# v1_r0.net
KiCad netlist of a schematic drawn in EAGLE
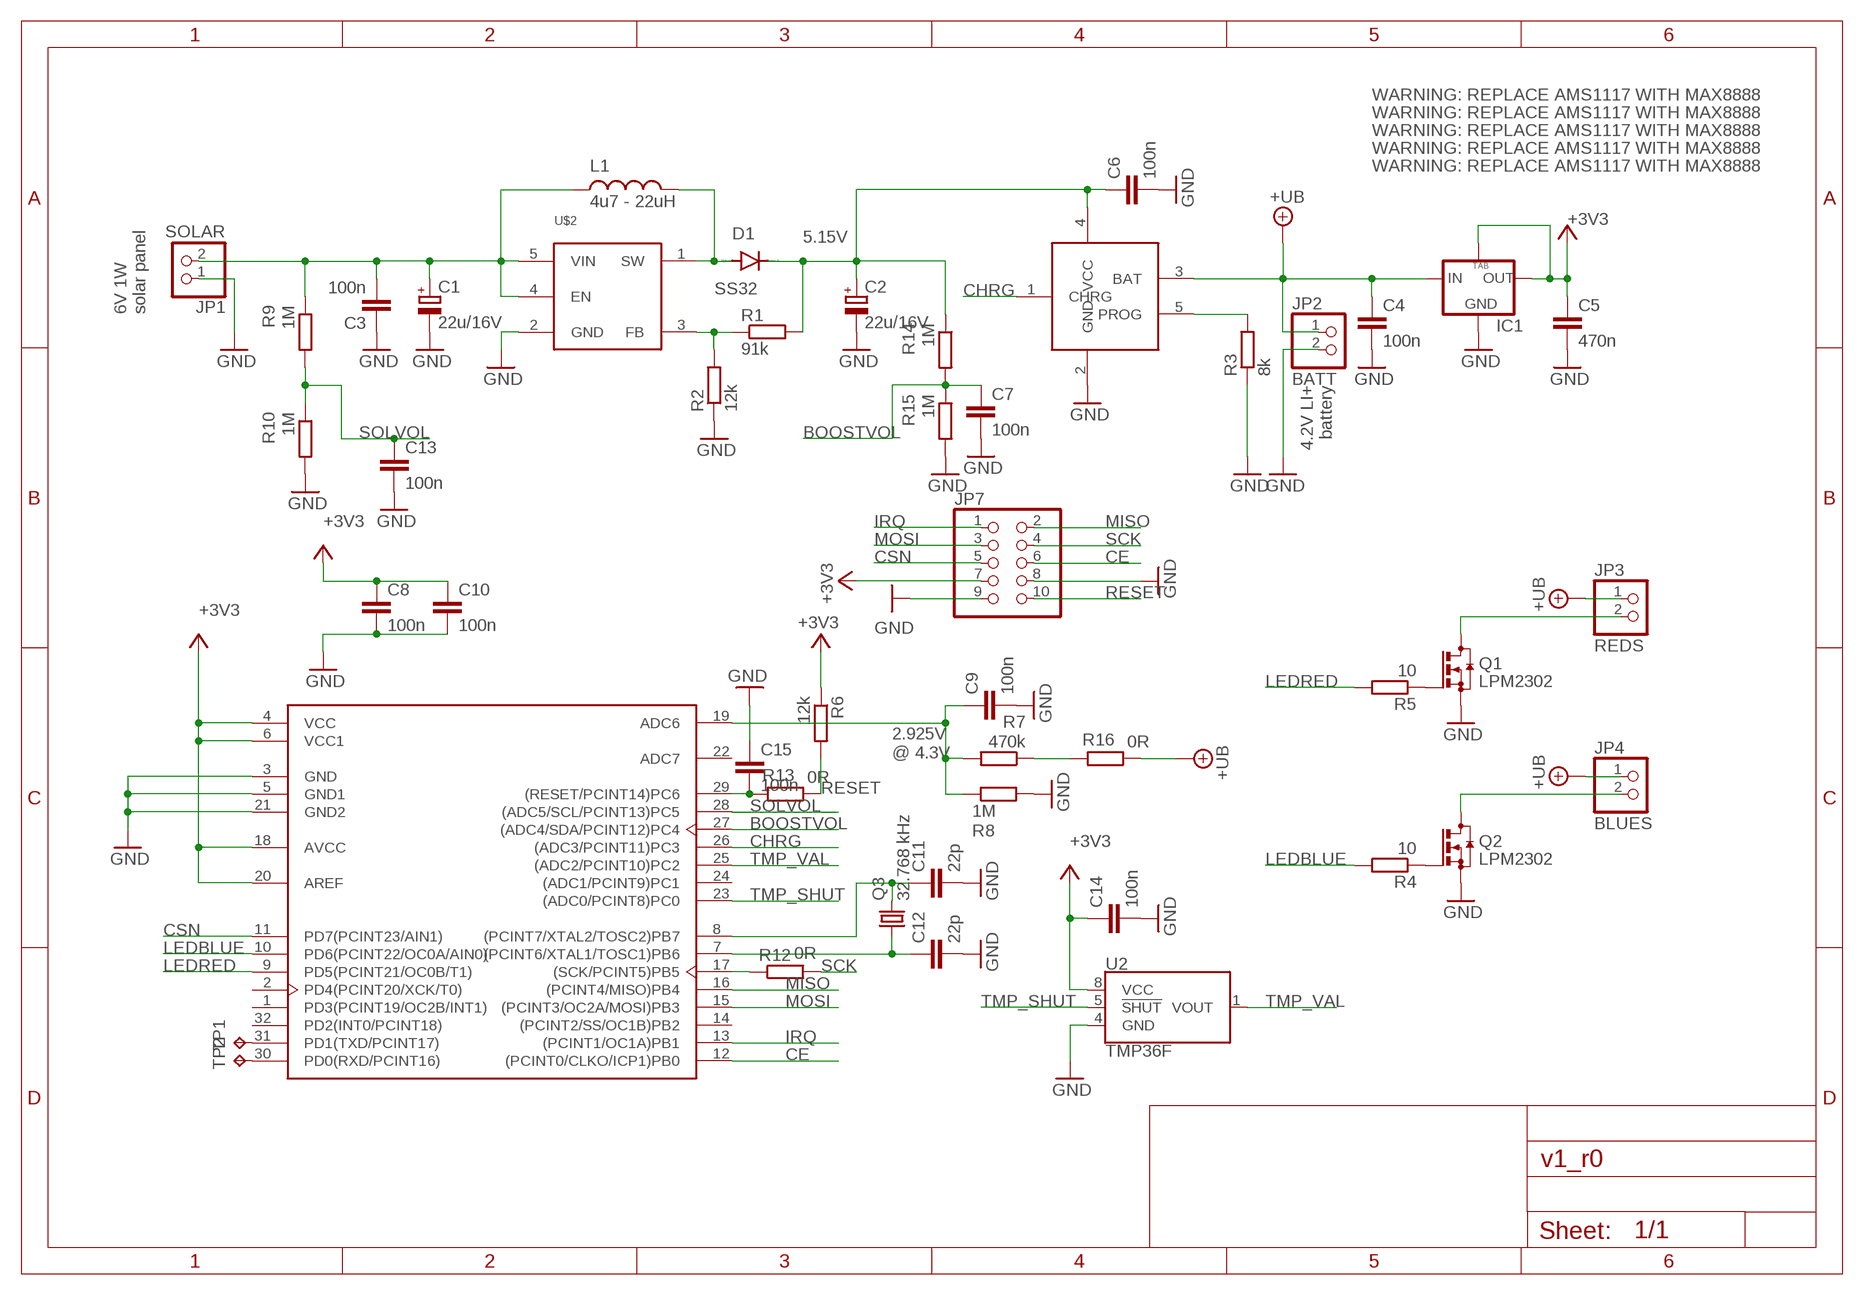
[diagram p0: schematic, sheet 1]

(export (version "E")
  (design (tool "Eeschema 10.0.6"))
  (components
    (comp (ref "C1")
      (value "22u/16V")
      (footprint "eagle-import:CT6032")
      (libsource (lib "eagle-import") (part "CPOL-EUCT6032"))
    )
    (comp (ref "C2")
      (value "22u/16V")
      (footprint "eagle-import:CT6032")
      (libsource (lib "eagle-import") (part "CPOL-EUCT6032"))
    )
    (comp (ref "C3")
      (value "100n")
      (footprint "eagle-import:C0603")
      (libsource (lib "eagle-import") (part "C-EUC0603"))
    )
    (comp (ref "C4")
      (value "100n")
      (footprint "eagle-import:C0603")
      (libsource (lib "eagle-import") (part "C-EUC0603"))
    )
    (comp (ref "C5")
      (value "470n")
      (footprint "eagle-import:C0603")
      (libsource (lib "eagle-import") (part "C-EUC0603"))
    )
    (comp (ref "C6")
      (value "100n")
      (footprint "eagle-import:C0603")
      (libsource (lib "eagle-import") (part "C-EUC0603"))
    )
    (comp (ref "C7")
      (value "100n")
      (footprint "eagle-import:C0603")
      (libsource (lib "eagle-import") (part "C-EUC0603"))
    )
    (comp (ref "C8")
      (value "100n")
      (footprint "eagle-import:C0603")
      (libsource (lib "eagle-import") (part "C-EUC0603"))
    )
    (comp (ref "C9")
      (value "100n")
      (footprint "eagle-import:C0603")
      (libsource (lib "eagle-import") (part "C-EUC0603"))
    )
    (comp (ref "C10")
      (value "100n")
      (footprint "eagle-import:C0603")
      (libsource (lib "eagle-import") (part "C-EUC0603"))
    )
    (comp (ref "C11")
      (value "22p")
      (footprint "eagle-import:C0603")
      (libsource (lib "eagle-import") (part "C-EUC0603"))
    )
    (comp (ref "C12")
      (value "22p")
      (footprint "eagle-import:C0603")
      (libsource (lib "eagle-import") (part "C-EUC0603"))
    )
    (comp (ref "C13")
      (value "100n")
      (footprint "eagle-import:C0603")
      (libsource (lib "eagle-import") (part "C-EUC0603"))
    )
    (comp (ref "C14")
      (value "100n")
      (footprint "eagle-import:C0603")
      (libsource (lib "eagle-import") (part "C-EUC0603"))
    )
    (comp (ref "C15")
      (value "100n")
      (footprint "eagle-import:C0603")
      (libsource (lib "eagle-import") (part "C-EUC0603"))
    )
    (comp (ref "D1")
      (value "SS32")
      (footprint "eagle-import:SMB")
      (libsource (lib "eagle-import") (part "ES2D"))
    )
    (comp (ref "IC1")
      (value "LM1117")
      (footprint "eagle-import:SOT223")
      (libsource (lib "eagle-import") (part "LM1117"))
    )
    (comp (ref "JP1")
      (value "SOLAR")
      (footprint "eagle-import:1X02")
      (libsource (lib "eagle-import") (part "PINHD-1X2"))
    )
    (comp (ref "JP2")
      (value "BATT")
      (footprint "eagle-import:1X02")
      (libsource (lib "eagle-import") (part "PINHD-1X2"))
    )
    (comp (ref "JP3")
      (value "REDS")
      (footprint "eagle-import:1X02")
      (libsource (lib "eagle-import") (part "PINHD-1X2"))
    )
    (comp (ref "JP4")
      (value "BLUES")
      (footprint "eagle-import:1X02")
      (libsource (lib "eagle-import") (part "PINHD-1X2"))
    )
    (comp (ref "JP7")
      (value "PINHD-2X5")
      (footprint "eagle-import:2X05")
      (libsource (lib "eagle-import") (part "PINHD-2X5"))
    )
    (comp (ref "L1")
      (value "4u7 - 22uH")
      (footprint "eagle-import:DS1608")
      (libsource (lib "eagle-import") (part "DS1608C"))
    )
    (comp (ref "Q1")
      (value "LPM2302")
      (footprint "eagle-import:SOT23")
      (libsource (lib "eagle-import") (part "BSS123"))
    )
    (comp (ref "Q2")
      (value "LPM2302")
      (footprint "eagle-import:SOT23")
      (libsource (lib "eagle-import") (part "BSS123"))
    )
    (comp (ref "Q3")
      (value "32.768 kHz")
      (footprint "eagle-import:CTS406")
      (libsource (lib "eagle-import") (part "CRYSTALCTS406"))
    )
    (comp (ref "R1")
      (value "91k")
      (footprint "eagle-import:R0603")
      (libsource (lib "eagle-import") (part "R-EU_R0603"))
    )
    (comp (ref "R2")
      (value "12k")
      (footprint "eagle-import:R0603")
      (libsource (lib "eagle-import") (part "R-EU_R0603"))
    )
    (comp (ref "R3")
      (value "8k")
      (footprint "eagle-import:R0603")
      (libsource (lib "eagle-import") (part "R-EU_R0603"))
    )
    (comp (ref "R4")
      (value "10")
      (footprint "eagle-import:R0603")
      (libsource (lib "eagle-import") (part "R-EU_R0603"))
    )
    (comp (ref "R5")
      (value "10")
      (footprint "eagle-import:R0603")
      (libsource (lib "eagle-import") (part "R-EU_R0603"))
    )
    (comp (ref "R6")
      (value "12k")
      (footprint "eagle-import:R0603")
      (libsource (lib "eagle-import") (part "R-EU_R0603"))
    )
    (comp (ref "R7")
      (value "470k")
      (footprint "eagle-import:R0603")
      (libsource (lib "eagle-import") (part "R-EU_R0603"))
    )
    (comp (ref "R8")
      (value "1M")
      (footprint "eagle-import:R0603")
      (libsource (lib "eagle-import") (part "R-EU_R0603"))
    )
    (comp (ref "R9")
      (value "1M")
      (footprint "eagle-import:R0603")
      (libsource (lib "eagle-import") (part "R-EU_R0603"))
    )
    (comp (ref "R10")
      (value "1M")
      (footprint "eagle-import:R0603")
      (libsource (lib "eagle-import") (part "R-EU_R0603"))
    )
    (comp (ref "R12")
      (value "0R")
      (footprint "eagle-import:0204_5")
      (libsource (lib "eagle-import") (part "resistor_348_R-EU_0204/5"))
    )
    (comp (ref "R13")
      (value "0R")
      (footprint "eagle-import:0204_5")
      (libsource (lib "eagle-import") (part "resistor_348_R-EU_0204/5"))
    )
    (comp (ref "R14")
      (value "1M")
      (footprint "eagle-import:R0603")
      (libsource (lib "eagle-import") (part "R-EU_R0603"))
    )
    (comp (ref "R15")
      (value "1M")
      (footprint "eagle-import:R0603")
      (libsource (lib "eagle-import") (part "R-EU_R0603"))
    )
    (comp (ref "R16")
      (value "0R")
      (footprint "eagle-import:0204_5")
      (libsource (lib "eagle-import") (part "resistor_348_R-EU_0204/5"))
    )
    (comp (ref "TP1")
      (value "TPB1,27")
      (footprint "eagle-import:B1,27")
      (libsource (lib "eagle-import") (part "TPB1,27"))
    )
    (comp (ref "TP2")
      (value "TPB1,27")
      (footprint "eagle-import:B1,27")
      (libsource (lib "eagle-import") (part "TPB1,27"))
    )
    (comp (ref "U$1")
      (value "LTC4054")
      (footprint "eagle-import:LTC4054")
      (libsource (lib "eagle-import") (part "LTC4054"))
    )
    (comp (ref "U$2")
      (value "SB6284")
      (footprint "eagle-import:SOT23-6")
      (libsource (lib "eagle-import") (part "SB6284"))
    )
    (comp (ref "U1")
      (value "ATMEGA*")
      (footprint "eagle-import:TQFP-32")
      (fields
        (field (name "DIGIKEY_PART_NUMBER") "ATMEGA328P-AU-ND")
        (field (name "MANUFACTURER") "Microchip Technology")
        (field (name "MPN") "ATMEGA328P-AU")
        (field (name "CREATED_BY") "PCBLayout.com")
      )
      (libsource (lib "eagle-import") (part "ATMEGA328P-AU"))
    )
    (comp (ref "U2")
      (value "TMP36F")
      (footprint "eagle-import:SOIC-8")
      (libsource (lib "eagle-import") (part "TMP36"))
    )
  )
  (nets
    (net (code "1") (name "+3V3") (class "Default")
      (node (ref "C10") (pin "1") (pinfunction "1_1") (pintype "passive"))
      (node (ref "C14") (pin "1") (pinfunction "1_1") (pintype "passive"))
      (node (ref "C5") (pin "1") (pinfunction "1_1") (pintype "passive"))
      (node (ref "C8") (pin "1") (pinfunction "1_1") (pintype "passive"))
      (node (ref "IC1") (pin "2") (pinfunction "OUT_2") (pintype "passive"))
      (node (ref "IC1") (pin "4") (pinfunction "TAB_4") (pintype "passive"))
      (node (ref "JP7") (pin "7") (pinfunction "7_7") (pintype "passive"))
      (node (ref "R6") (pin "1") (pinfunction "1_1") (pintype "passive"))
      (node (ref "U1") (pin "18") (pinfunction "AVCC_18") (pintype "power_in"))
      (node (ref "U1") (pin "20") (pinfunction "AREF_20") (pintype "power_in"))
      (node (ref "U1") (pin "4") (pinfunction "VCC_4") (pintype "power_in"))
      (node (ref "U1") (pin "6") (pinfunction "VCC1_6") (pintype "power_in"))
      (node (ref "U2") (pin "8") (pinfunction "VCC_8") (pintype "bidirectional"))
    )
    (net (code "2") (name "+UB") (class "Default")
      (node (ref "C4") (pin "1") (pinfunction "1_1") (pintype "passive"))
      (node (ref "IC1") (pin "3") (pinfunction "IN_3") (pintype "input"))
      (node (ref "JP2") (pin "1") (pinfunction "1_1") (pintype "passive"))
      (node (ref "JP3") (pin "1") (pinfunction "1_1") (pintype "passive"))
      (node (ref "JP4") (pin "1") (pinfunction "1_1") (pintype "passive"))
      (node (ref "R16") (pin "1") (pinfunction "1_1") (pintype "passive"))
      (node (ref "U$1") (pin "3") (pinfunction "BAT_3") (pintype "output"))
    )
    (net (code "3") (name "/BOOSTVOL") (class "Default")
      (node (ref "C7") (pin "1") (pinfunction "1_1") (pintype "passive"))
      (node (ref "R14") (pin "2") (pinfunction "2_2") (pintype "passive"))
      (node (ref "R15") (pin "1") (pinfunction "1_1") (pintype "passive"))
      (node (ref "U1") (pin "27") (pinfunction "(ADC4/SDA/PCINT12)PC4_27") (pintype "bidirectional"))
    )
    (net (code "4") (name "/CE") (class "Default")
      (node (ref "JP7") (pin "6") (pinfunction "6_6") (pintype "passive"))
      (node (ref "U1") (pin "12") (pinfunction "(PCINT0/CLKO/ICP1)PB0_12") (pintype "bidirectional"))
    )
    (net (code "5") (name "/CHRG") (class "Default")
      (node (ref "U$1") (pin "1") (pinfunction "CHRG_1") (pintype "bidirectional"))
      (node (ref "U1") (pin "26") (pinfunction "(ADC3/PCINT11)PC3_26") (pintype "bidirectional"))
    )
    (net (code "6") (name "/CSN") (class "Default")
      (node (ref "JP7") (pin "5") (pinfunction "5_5") (pintype "passive"))
      (node (ref "U1") (pin "11") (pinfunction "PD7(PCINT23/AIN1)_11") (pintype "bidirectional"))
    )
    (net (code "7") (name "/IRQ") (class "Default")
      (node (ref "JP7") (pin "1") (pinfunction "1_1") (pintype "passive"))
      (node (ref "U1") (pin "13") (pinfunction "(PCINT1/OC1A)PB1_13") (pintype "bidirectional"))
    )
    (net (code "8") (name "/LEDBLUE") (class "Default")
      (node (ref "R4") (pin "2") (pinfunction "2_2") (pintype "passive"))
      (node (ref "U1") (pin "10") (pinfunction "PD6(PCINT22/OC0A/AIN0)_10") (pintype "bidirectional"))
    )
    (net (code "9") (name "/LEDRED") (class "Default")
      (node (ref "R5") (pin "2") (pinfunction "2_2") (pintype "passive"))
      (node (ref "U1") (pin "9") (pinfunction "PD5(PCINT21/OC0B/T1)_9") (pintype "bidirectional"))
    )
    (net (code "10") (name "/MISO") (class "Default")
      (node (ref "JP7") (pin "2") (pinfunction "2_2") (pintype "passive"))
      (node (ref "U1") (pin "16") (pinfunction "(PCINT4/MISO)PB4_16") (pintype "bidirectional"))
    )
    (net (code "11") (name "/MOSI") (class "Default")
      (node (ref "JP7") (pin "3") (pinfunction "3_3") (pintype "passive"))
      (node (ref "U1") (pin "15") (pinfunction "(PCINT3/OC2A/MOSI)PB3_15") (pintype "bidirectional"))
    )
    (net (code "12") (name "/RESET") (class "Default")
      (node (ref "JP7") (pin "10") (pinfunction "10_10") (pintype "passive"))
      (node (ref "R13") (pin "1") (pinfunction "1_1") (pintype "passive"))
      (node (ref "R6") (pin "2") (pinfunction "2_2") (pintype "passive"))
    )
    (net (code "13") (name "/SCK") (class "Default")
      (node (ref "JP7") (pin "4") (pinfunction "4_4") (pintype "passive"))
      (node (ref "R12") (pin "2") (pinfunction "2_2") (pintype "passive"))
    )
    (net (code "14") (name "/SOLVOL") (class "Default")
      (node (ref "C13") (pin "1") (pinfunction "1_1") (pintype "passive"))
      (node (ref "R10") (pin "1") (pinfunction "1_1") (pintype "passive"))
      (node (ref "R9") (pin "2") (pinfunction "2_2") (pintype "passive"))
      (node (ref "U1") (pin "28") (pinfunction "(ADC5/SCL/PCINT13)PC5_28") (pintype "bidirectional"))
    )
    (net (code "15") (name "/TMP_SHUT") (class "Default")
      (node (ref "U1") (pin "23") (pinfunction "(ADC0/PCINT8)PC0_23") (pintype "bidirectional"))
      (node (ref "U2") (pin "5") (pinfunction "~{SHUT}_5") (pintype "bidirectional"))
    )
    (net (code "16") (name "/TMP_VAL") (class "Default")
      (node (ref "U1") (pin "25") (pinfunction "(ADC2/PCINT10)PC2_25") (pintype "bidirectional"))
      (node (ref "U2") (pin "1") (pinfunction "VOUT_1") (pintype "bidirectional"))
    )
    (net (code "17") (name "GND") (class "Default")
      (node (ref "C1") (pin "-") (pinfunction "-_-") (pintype "passive"))
      (node (ref "C10") (pin "2") (pinfunction "2_2") (pintype "passive"))
      (node (ref "C11") (pin "2") (pinfunction "2_2") (pintype "passive"))
      (node (ref "C12") (pin "2") (pinfunction "2_2") (pintype "passive"))
      (node (ref "C13") (pin "2") (pinfunction "2_2") (pintype "passive"))
      (node (ref "C14") (pin "2") (pinfunction "2_2") (pintype "passive"))
      (node (ref "C15") (pin "1") (pinfunction "1_1") (pintype "passive"))
      (node (ref "C2") (pin "-") (pinfunction "-_-") (pintype "passive"))
      (node (ref "C3") (pin "1") (pinfunction "1_1") (pintype "passive"))
      (node (ref "C4") (pin "2") (pinfunction "2_2") (pintype "passive"))
      (node (ref "C5") (pin "2") (pinfunction "2_2") (pintype "passive"))
      (node (ref "C6") (pin "2") (pinfunction "2_2") (pintype "passive"))
      (node (ref "C7") (pin "2") (pinfunction "2_2") (pintype "passive"))
      (node (ref "C8") (pin "2") (pinfunction "2_2") (pintype "passive"))
      (node (ref "C9") (pin "2") (pinfunction "2_2") (pintype "passive"))
      (node (ref "IC1") (pin "1") (pinfunction "GND_1") (pintype "input"))
      (node (ref "JP1") (pin "1") (pinfunction "1_1") (pintype "passive"))
      (node (ref "JP2") (pin "2") (pinfunction "2_2") (pintype "passive"))
      (node (ref "JP7") (pin "8") (pinfunction "8_8") (pintype "passive"))
      (node (ref "JP7") (pin "9") (pinfunction "9_9") (pintype "passive"))
      (node (ref "Q1") (pin "2") (pinfunction "S_2") (pintype "passive"))
      (node (ref "Q2") (pin "2") (pinfunction "S_2") (pintype "passive"))
      (node (ref "R10") (pin "2") (pinfunction "2_2") (pintype "passive"))
      (node (ref "R15") (pin "2") (pinfunction "2_2") (pintype "passive"))
      (node (ref "R2") (pin "1") (pinfunction "1_1") (pintype "passive"))
      (node (ref "R3") (pin "1") (pinfunction "1_1") (pintype "passive"))
      (node (ref "R8") (pin "2") (pinfunction "2_2") (pintype "passive"))
      (node (ref "U$1") (pin "2") (pinfunction "GND_2") (pintype "power_in"))
      (node (ref "U$2") (pin "2") (pinfunction "GND_2") (pintype "bidirectional"))
      (node (ref "U1") (pin "21") (pinfunction "GND2_21") (pintype "power_in"))
      (node (ref "U1") (pin "3") (pinfunction "GND_3") (pintype "power_in"))
      (node (ref "U1") (pin "5") (pinfunction "GND1_5") (pintype "power_in"))
      (node (ref "U2") (pin "4") (pinfunction "GND_4") (pintype "bidirectional"))
    )
    (net (code "18") (name "Net-(Q1-D)") (class "Default")
      (node (ref "JP3") (pin "2") (pinfunction "2_2") (pintype "passive"))
      (node (ref "Q1") (pin "3") (pinfunction "D_3") (pintype "passive"))
    )
    (net (code "19") (name "Net-(Q1-G)") (class "Default")
      (node (ref "Q1") (pin "1") (pinfunction "G_1") (pintype "passive"))
      (node (ref "R5") (pin "1") (pinfunction "1_1") (pintype "passive"))
    )
    (net (code "20") (name "Net-(Q2-D)") (class "Default")
      (node (ref "JP4") (pin "2") (pinfunction "2_2") (pintype "passive"))
      (node (ref "Q2") (pin "3") (pinfunction "D_3") (pintype "passive"))
    )
    (net (code "21") (name "Net-(Q2-G)") (class "Default")
      (node (ref "Q2") (pin "1") (pinfunction "G_1") (pintype "passive"))
      (node (ref "R4") (pin "1") (pinfunction "1_1") (pintype "passive"))
    )
    (net (code "22") (name "Net-(Q3-2)") (class "Default")
      (node (ref "C11") (pin "1") (pinfunction "1_1") (pintype "passive"))
      (node (ref "Q3") (pin "3") (pinfunction "2_3") (pintype "passive"))
      (node (ref "U1") (pin "8") (pinfunction "(PCINT7/XTAL2/TOSC2)PB7_8") (pintype "bidirectional"))
    )
    (net (code "23") (name "Net-(R16-Pad2)") (class "Default")
      (node (ref "R16") (pin "2") (pinfunction "2_2") (pintype "passive"))
      (node (ref "R7") (pin "1") (pinfunction "1_1") (pintype "passive"))
    )
    (net (code "24") (name "Net-(U$1-PROG)") (class "Default")
      (node (ref "R3") (pin "2") (pinfunction "2_2") (pintype "passive"))
      (node (ref "U$1") (pin "5") (pinfunction "PROG_5") (pintype "bidirectional"))
    )
    (net (code "25") (name "Net-(U$1-VCC)") (class "Default")
      (node (ref "C2") (pin "+") (pinfunction "+_+") (pintype "passive"))
      (node (ref "C6") (pin "1") (pinfunction "1_1") (pintype "passive"))
      (node (ref "D1") (pin "C") (pinfunction "C_C") (pintype "passive"))
      (node (ref "R1") (pin "2") (pinfunction "2_2") (pintype "passive"))
      (node (ref "R14") (pin "1") (pinfunction "1_1") (pintype "passive"))
      (node (ref "U$1") (pin "4") (pinfunction "VCC_4") (pintype "power_in"))
    )
    (net (code "26") (name "Net-(U$2-EN)") (class "Default")
      (node (ref "C1") (pin "+") (pinfunction "+_+") (pintype "passive"))
      (node (ref "C3") (pin "2") (pinfunction "2_2") (pintype "passive"))
      (node (ref "JP1") (pin "2") (pinfunction "2_2") (pintype "passive"))
      (node (ref "L1") (pin "P$2") (pinfunction "P$2_P$2") (pintype "passive"))
      (node (ref "R9") (pin "1") (pinfunction "1_1") (pintype "passive"))
      (node (ref "U$2") (pin "4") (pinfunction "EN_4") (pintype "bidirectional"))
      (node (ref "U$2") (pin "5") (pinfunction "VIN_5") (pintype "power_in"))
    )
    (net (code "27") (name "Net-(U$2-FB)") (class "Default")
      (node (ref "R1") (pin "1") (pinfunction "1_1") (pintype "passive"))
      (node (ref "R2") (pin "2") (pinfunction "2_2") (pintype "passive"))
      (node (ref "U$2") (pin "3") (pinfunction "FB_3") (pintype "bidirectional"))
    )
    (net (code "28") (name "Net-(U$2-SW)") (class "Default")
      (node (ref "D1") (pin "A") (pinfunction "A_A") (pintype "passive"))
      (node (ref "L1") (pin "P$1") (pinfunction "P$1_P$1") (pintype "passive"))
      (node (ref "U$2") (pin "1") (pinfunction "SW_1") (pintype "bidirectional"))
    )
    (net (code "29") (name "Net-(U1-(PCINT6{slash}XTAL1{slash}TOSC1)PB6)") (class "Default")
      (node (ref "C12") (pin "1") (pinfunction "1_1") (pintype "passive"))
      (node (ref "Q3") (pin "1") (pinfunction "1_1") (pintype "passive"))
      (node (ref "U1") (pin "7") (pinfunction "(PCINT6/XTAL1/TOSC1)PB6_7") (pintype "bidirectional"))
    )
    (net (code "30") (name "Net-(U1-(RESET{slash}PCINT14)PC6)") (class "Default")
      (node (ref "C15") (pin "2") (pinfunction "2_2") (pintype "passive"))
      (node (ref "R13") (pin "2") (pinfunction "2_2") (pintype "passive"))
      (node (ref "U1") (pin "29") (pinfunction "(RESET/PCINT14)PC6_29") (pintype "bidirectional"))
    )
    (net (code "31") (name "Net-(U1-(SCK{slash}PCINT5)PB5)") (class "Default")
      (node (ref "R12") (pin "1") (pinfunction "1_1") (pintype "passive"))
      (node (ref "U1") (pin "17") (pinfunction "(SCK/PCINT5)PB5_17") (pintype "bidirectional"))
    )
    (net (code "32") (name "Net-(U1-ADC6)") (class "Default")
      (node (ref "C9") (pin "1") (pinfunction "1_1") (pintype "passive"))
      (node (ref "R7") (pin "2") (pinfunction "2_2") (pintype "passive"))
      (node (ref "R8") (pin "1") (pinfunction "1_1") (pintype "passive"))
      (node (ref "U1") (pin "19") (pinfunction "ADC6_19") (pintype "input"))
    )
    (net (code "33") (name "Net-(U1-PD0(RXD{slash}PCINT16))") (class "Default")
      (node (ref "TP2") (pin "TP") (pinfunction "TP_TP") (pintype "input"))
      (node (ref "U1") (pin "30") (pinfunction "PD0(RXD/PCINT16)_30") (pintype "bidirectional"))
    )
    (net (code "34") (name "Net-(U1-PD1(TXD{slash}PCINT17))") (class "Default")
      (node (ref "TP1") (pin "TP") (pinfunction "TP_TP") (pintype "input"))
      (node (ref "U1") (pin "31") (pinfunction "PD1(TXD/PCINT17)_31") (pintype "bidirectional"))
    )
    (net (code "35") (name "unconnected-(U1-(ADC1{slash}PCINT9)PC1-Pad24)") (class "Default")
      (node (ref "U1") (pin "24") (pinfunction "(ADC1/PCINT9)PC1_24") (pintype "bidirectional"))
    )
    (net (code "36") (name "unconnected-(U1-(PCINT2{slash}SS{slash}OC1B)PB2-Pad14)") (class "Default")
      (node (ref "U1") (pin "14") (pinfunction "(PCINT2/SS/OC1B)PB2_14") (pintype "bidirectional"))
    )
    (net (code "37") (name "unconnected-(U1-ADC7-Pad22)") (class "Default")
      (node (ref "U1") (pin "22") (pinfunction "ADC7_22") (pintype "input"))
    )
    (net (code "38") (name "unconnected-(U1-PD2(INT0{slash}PCINT18)-Pad32)") (class "Default")
      (node (ref "U1") (pin "32") (pinfunction "PD2(INT0/PCINT18)_32") (pintype "bidirectional"))
    )
    (net (code "39") (name "unconnected-(U1-PD3(PCINT19{slash}OC2B{slash}INT1)-Pad1)") (class "Default")
      (node (ref "U1") (pin "1") (pinfunction "PD3(PCINT19/OC2B/INT1)_1") (pintype "bidirectional"))
    )
    (net (code "40") (name "unconnected-(U1-PD4(PCINT20{slash}XCK{slash}T0)-Pad2)") (class "Default")
      (node (ref "U1") (pin "2") (pinfunction "PD4(PCINT20/XCK/T0)_2") (pintype "bidirectional"))
    )
  )
)
